# Group14StepperMotorDriver.net
KiCad netlist of a schematic drawn in Altium Designer
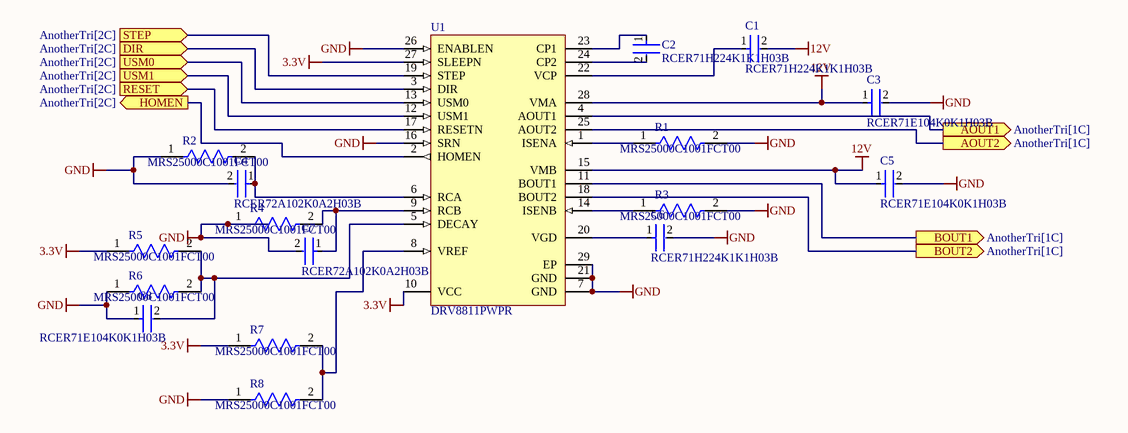
[diagram p0: Group14StepperMotorDriver.SchDoc]

(export (version "E")
  (design (tool "Eeschema 10.0.6"))
  (components
    (comp (ref "C1")
      (value "RCER71H224K1K1H03B")
      (footprint "FP-RCE1K1-2_5-MFG")
      (description "Cap Ceramic Monolithic 220nF 50V 10% Thru-Hole Bulk")
      (fields (field (name "TOLERANCE") "10%"))
      (libsource (lib "Altium Content Vault") (part "02cd4be3c70576c341d710602a673aa"))
    )
    (comp (ref "C2")
      (value "RCER71H224K1K1H03B")
      (footprint "FP-RCE1K1-2_5-MFG")
      (description "Cap Ceramic Monolithic 220nF 50V 10% Thru-Hole Bulk")
      (fields (field (name "TOLERANCE") "10%"))
      (libsource (lib "Altium Content Vault") (part "02cd4be3c70576c341d710602a673aa"))
    )
    (comp (ref "C3")
      (value "RCER71E104K0K1H03B")
      (footprint "FP-RCE0K1-MFG")
      (description "Cap Ceramic 100nF 25V X7R ±10% Radial 5mm +125°C Automotive Bulk")
      (libsource (lib "Altium Content Vault") (part "b4654b650e69147ec39a6b967a45e02"))
    )
    (comp (ref "C4")
      (value "RCER72A102K0A2H03B")
      (footprint "FP-RCE0DB-MFG")
      (description "Cap Ceramic 1nF 100V X7R ±10% Radial 2.5mm +125°C Bulk")
      (fields (field (name "TOLERANCE") "10%"))
      (libsource (lib "Altium Content Vault") (part "b4654b650e69147ec39a6b967a45e02"))
    )
    (comp (ref "C5")
      (value "RCER71E104K0K1H03B")
      (footprint "FP-RCE0K1-MFG")
      (description "Cap Ceramic 100nF 25V X7R ±10% Radial 5mm +125°C Automotive Bulk")
      (libsource (lib "Altium Content Vault") (part "b4654b650e69147ec39a6b967a45e02"))
    )
    (comp (ref "C6")
      (value "RCER71H224K1K1H03B")
      (footprint "FP-RCE1K1-2_5-MFG")
      (description "Cap Ceramic Monolithic 220nF 50V 10% Thru-Hole Bulk")
      (fields (field (name "TOLERANCE") "10%"))
      (libsource (lib "Altium Content Vault") (part "02cd4be3c70576c341d710602a673aa"))
    )
    (comp (ref "C7")
      (value "RCER72A102K0A2H03B")
      (footprint "FP-RCE0DB-MFG")
      (description "Cap Ceramic 1nF 100V X7R ±10% Radial 2.5mm +125°C Bulk")
      (fields (field (name "TOLERANCE") "10%"))
      (libsource (lib "Altium Content Vault") (part "b4654b650e69147ec39a6b967a45e02"))
    )
    (comp (ref "C8")
      (value "RCER71E104K0K1H03B")
      (footprint "FP-RCE0K1-MFG")
      (description "Cap Ceramic 100nF 25V X7R ±10% Radial 5mm +125°C Automotive Bulk")
      (libsource (lib "Altium Content Vault") (part "b4654b650e69147ec39a6b967a45e02"))
    )
    (comp (ref "R1")
      (value "MRS25000C1001FCT00")
      (footprint "FP-MRS25-MFG")
      (description "RES 1K OHM 0.6W 1% AXIAL")
      (fields (field (name "TOLERANCE") "1%"))
      (libsource (lib "Altium Content Vault") (part "1029c3af85768c4190bb7ad29bc67b5"))
    )
    (comp (ref "R2")
      (value "MRS25000C1001FCT00")
      (footprint "FP-MRS25-MFG")
      (description "RES 1K OHM 0.6W 1% AXIAL")
      (fields (field (name "TOLERANCE") "1%"))
      (libsource (lib "Altium Content Vault") (part "1029c3af85768c4190bb7ad29bc67b5"))
    )
    (comp (ref "R3")
      (value "MRS25000C1001FCT00")
      (footprint "FP-MRS25-MFG")
      (description "RES 1K OHM 0.6W 1% AXIAL")
      (fields (field (name "TOLERANCE") "1%"))
      (libsource (lib "Altium Content Vault") (part "1029c3af85768c4190bb7ad29bc67b5"))
    )
    (comp (ref "R4")
      (value "MRS25000C1001FCT00")
      (footprint "FP-MRS25-MFG")
      (description "RES 1K OHM 0.6W 1% AXIAL")
      (fields (field (name "TOLERANCE") "1%"))
      (libsource (lib "Altium Content Vault") (part "1029c3af85768c4190bb7ad29bc67b5"))
    )
    (comp (ref "R5")
      (value "MRS25000C1001FCT00")
      (footprint "FP-MRS25-MFG")
      (description "RES 1K OHM 0.6W 1% AXIAL")
      (fields (field (name "TOLERANCE") "1%"))
      (libsource (lib "Altium Content Vault") (part "1029c3af85768c4190bb7ad29bc67b5"))
    )
    (comp (ref "R6")
      (value "MRS25000C1001FCT00")
      (footprint "FP-MRS25-MFG")
      (description "RES 1K OHM 0.6W 1% AXIAL")
      (fields (field (name "TOLERANCE") "1%"))
      (libsource (lib "Altium Content Vault") (part "1029c3af85768c4190bb7ad29bc67b5"))
    )
    (comp (ref "R7")
      (value "MRS25000C1001FCT00")
      (footprint "FP-MRS25-MFG")
      (description "RES 1K OHM 0.6W 1% AXIAL")
      (fields (field (name "TOLERANCE") "1%"))
      (libsource (lib "Altium Content Vault") (part "1029c3af85768c4190bb7ad29bc67b5"))
    )
    (comp (ref "R8")
      (value "MRS25000C1001FCT00")
      (footprint "FP-MRS25-MFG")
      (description "RES 1K OHM 0.6W 1% AXIAL")
      (fields (field (name "TOLERANCE") "1%"))
      (libsource (lib "Altium Content Vault") (part "1029c3af85768c4190bb7ad29bc67b5"))
    )
    (comp (ref "U1")
      (value "DRV8811PWPR")
      (footprint "PWP0028C_L")
      (libsource (lib "Altium Content Vault") (part "TI-DRV8811PWP28-5230X2750TP"))
    )
  )
  (nets
    (net (code "1") (name "/AOUT1") (class "Default")
      (node (ref "U1") (pin "4") (pinfunction "AOUT1_4") (pintype "power_in"))
    )
    (net (code "2") (name "/AOUT2") (class "Default")
      (node (ref "U1") (pin "25") (pinfunction "AOUT2_25") (pintype "power_in"))
    )
    (net (code "3") (name "/BOUT1") (class "Default")
      (node (ref "U1") (pin "11") (pinfunction "BOUT1_11") (pintype "power_in"))
    )
    (net (code "4") (name "/BOUT2") (class "Default")
      (node (ref "U1") (pin "18") (pinfunction "BOUT2_18") (pintype "power_in"))
    )
    (net (code "5") (name "/DIR") (class "Default")
      (node (ref "U1") (pin "3") (pinfunction "DIR_3") (pintype "input"))
    )
    (net (code "6") (name "/HOMEN") (class "Default")
      (node (ref "U1") (pin "2") (pinfunction "HOMEN_2") (pintype "output"))
    )
    (net (code "7") (name "/RESET") (class "Default")
      (node (ref "U1") (pin "17") (pinfunction "RESETN_17") (pintype "input"))
    )
    (net (code "8") (name "/STEP") (class "Default")
      (node (ref "U1") (pin "19") (pinfunction "STEP_19") (pintype "input"))
    )
    (net (code "9") (name "/USM0") (class "Default")
      (node (ref "U1") (pin "13") (pinfunction "USM0_13") (pintype "input"))
    )
    (net (code "10") (name "/USM1") (class "Default")
      (node (ref "U1") (pin "12") (pinfunction "USM1_12") (pintype "input"))
    )
    (net (code "11") (name "3.3V") (class "Default")
      (node (ref "R5") (pin "1") (pinfunction "1_1") (pintype "passive"))
      (node (ref "R7") (pin "1") (pinfunction "1_1") (pintype "passive"))
      (node (ref "U1") (pin "10") (pinfunction "VCC_10") (pintype "power_in"))
      (node (ref "U1") (pin "27") (pinfunction "SLEEPN_27") (pintype "input"))
    )
    (net (code "12") (name "12V") (class "Default")
      (node (ref "C1") (pin "2") (pinfunction "2_2") (pintype "passive"))
      (node (ref "C3") (pin "1") (pinfunction "1_1") (pintype "passive"))
      (node (ref "C5") (pin "1") (pinfunction "1_1") (pintype "passive"))
      (node (ref "U1") (pin "15") (pinfunction "VMB_15") (pintype "power_in"))
      (node (ref "U1") (pin "28") (pinfunction "VMA_28") (pintype "power_in"))
    )
    (net (code "13") (name "GND") (class "Default")
      (node (ref "C3") (pin "2") (pinfunction "2_2") (pintype "passive"))
      (node (ref "C4") (pin "2") (pinfunction "2_2") (pintype "passive"))
      (node (ref "C5") (pin "2") (pinfunction "2_2") (pintype "passive"))
      (node (ref "C6") (pin "2") (pinfunction "2_2") (pintype "passive"))
      (node (ref "C7") (pin "2") (pinfunction "2_2") (pintype "passive"))
      (node (ref "C8") (pin "1") (pinfunction "1_1") (pintype "passive"))
      (node (ref "R1") (pin "2") (pinfunction "2_2") (pintype "passive"))
      (node (ref "R2") (pin "1") (pinfunction "1_1") (pintype "passive"))
      (node (ref "R3") (pin "2") (pinfunction "2_2") (pintype "passive"))
      (node (ref "R4") (pin "1") (pinfunction "1_1") (pintype "passive"))
      (node (ref "R6") (pin "1") (pinfunction "1_1") (pintype "passive"))
      (node (ref "R8") (pin "1") (pinfunction "1_1") (pintype "passive"))
      (node (ref "U1") (pin "16") (pinfunction "SRN_16") (pintype "input"))
      (node (ref "U1") (pin "21") (pinfunction "GND_21") (pintype "power_in"))
      (node (ref "U1") (pin "26") (pinfunction "ENABLEN_26") (pintype "input"))
      (node (ref "U1") (pin "29") (pinfunction "EP_29") (pintype "power_in"))
      (node (ref "U1") (pin "7") (pinfunction "GND_7") (pintype "power_in"))
    )
    (net (code "14") (name "Net-(U1-CP1)") (class "Default")
      (node (ref "C2") (pin "1") (pinfunction "1_1") (pintype "passive"))
      (node (ref "U1") (pin "23") (pinfunction "CP1_23") (pintype "passive"))
    )
    (net (code "15") (name "Net-(U1-CP2)") (class "Default")
      (node (ref "C2") (pin "2") (pinfunction "2_2") (pintype "passive"))
      (node (ref "U1") (pin "24") (pinfunction "CP2_24") (pintype "passive"))
    )
    (net (code "16") (name "Net-(U1-DECAY)") (class "Default")
      (node (ref "C8") (pin "2") (pinfunction "2_2") (pintype "passive"))
      (node (ref "R5") (pin "2") (pinfunction "2_2") (pintype "passive"))
      (node (ref "R6") (pin "2") (pinfunction "2_2") (pintype "passive"))
      (node (ref "U1") (pin "5") (pinfunction "DECAY_5") (pintype "input"))
    )
    (net (code "17") (name "Net-(U1-ISENA)") (class "Default")
      (node (ref "R1") (pin "1") (pinfunction "1_1") (pintype "passive"))
      (node (ref "U1") (pin "1") (pinfunction "ISENA_1") (pintype "input"))
    )
    (net (code "18") (name "Net-(U1-ISENB)") (class "Default")
      (node (ref "R3") (pin "1") (pinfunction "1_1") (pintype "passive"))
      (node (ref "U1") (pin "14") (pinfunction "ISENB_14") (pintype "input"))
    )
    (net (code "19") (name "Net-(U1-RCA)") (class "Default")
      (node (ref "C4") (pin "1") (pinfunction "1_1") (pintype "passive"))
      (node (ref "R2") (pin "2") (pinfunction "2_2") (pintype "passive"))
      (node (ref "U1") (pin "6") (pinfunction "RCA_6") (pintype "input"))
    )
    (net (code "20") (name "Net-(U1-RCB)") (class "Default")
      (node (ref "C7") (pin "1") (pinfunction "1_1") (pintype "passive"))
      (node (ref "R4") (pin "2") (pinfunction "2_2") (pintype "passive"))
      (node (ref "U1") (pin "9") (pinfunction "RCB_9") (pintype "input"))
    )
    (net (code "21") (name "Net-(U1-VCP)") (class "Default")
      (node (ref "C1") (pin "1") (pinfunction "1_1") (pintype "passive"))
      (node (ref "U1") (pin "22") (pinfunction "VCP_22") (pintype "power_in"))
    )
    (net (code "22") (name "Net-(U1-VGD)") (class "Default")
      (node (ref "C6") (pin "1") (pinfunction "1_1") (pintype "passive"))
      (node (ref "U1") (pin "20") (pinfunction "VGD_20") (pintype "power_in"))
    )
    (net (code "23") (name "Net-(U1-VREF)") (class "Default")
      (node (ref "R7") (pin "2") (pinfunction "2_2") (pintype "passive"))
      (node (ref "R8") (pin "2") (pinfunction "2_2") (pintype "passive"))
      (node (ref "U1") (pin "8") (pinfunction "VREF_8") (pintype "input"))
    )
  )
)
